# Power_Supply.net
KiCad netlist of a schematic drawn in Altium Designer
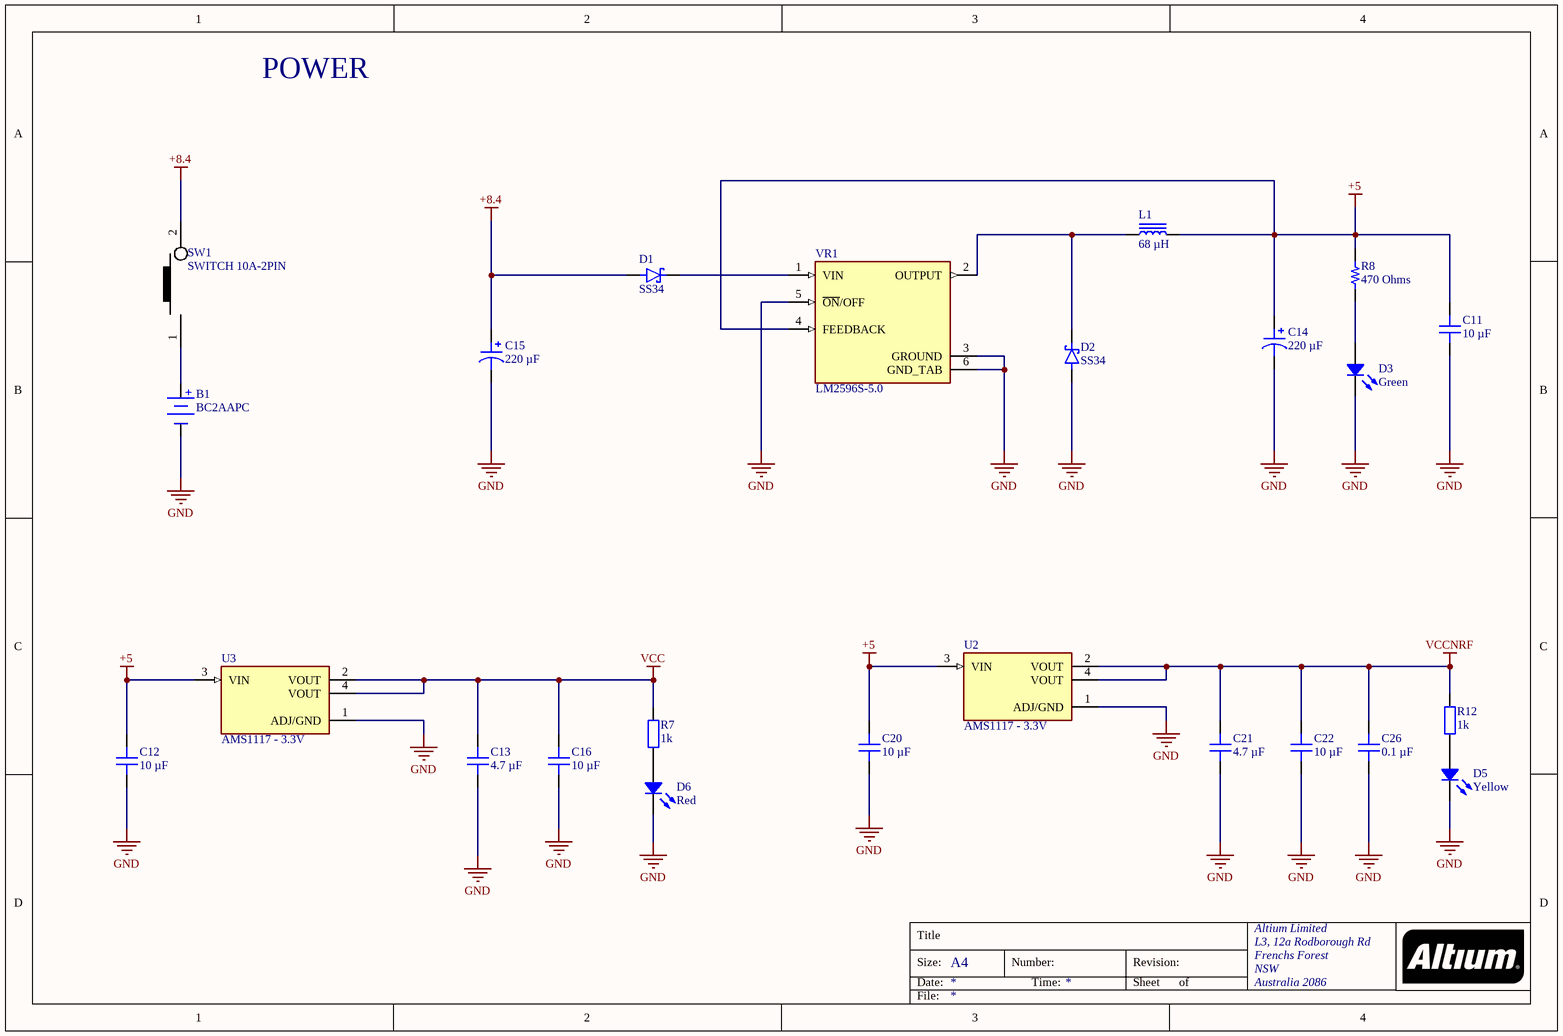
[diagram p0: Power_Supply.SchDoc]

(export (version "E")
  (design (tool "Eeschema 10.0.6"))
  (components
    (comp (ref "B1")
      (value "BC2AAPC")
      (footprint "MPD BC2AAPC")
      (description "BATTERY HOLDER AA 2 CELL PC PIN")
      (fields (field (name "MANUFACTURER") "MPD (Memory Protection Devices)"))
      (libsource (lib "Celestial Altium Library - altium_library") (part "MPD BC2AAPC"))
    )
    (comp (ref "C11")
      (value "10 µF")
      (footprint "CAP 0603_1608")
      (description "CAP CER 10UF 25V X5R 0603")
      (fields (field (name "PART NUMBER") "TMK107BBJ106MA-T") (field (name "MANUFACTURER") "Taiyo Yuden"))
      (libsource (lib "Celestial Altium Library - altium_library") (part "Capacitor"))
    )
    (comp (ref "C12")
      (value "10 µF")
      (footprint "CAP 0603_1608")
      (description "CAP CER 10UF 10V X6S 0603")
      (fields
        (field (name "PART NUMBER") "GRM188C81A106MA73D")
        (field (name "MANUFACTURER") "Murata Electronics")
      )
      (libsource (lib "Celestial Altium Library - altium_library") (part "Capacitor"))
    )
    (comp (ref "C13")
      (value "4.7 µF")
      (footprint "CAP 0603_1608")
      (description "CAP CER 4.7UF 10V X5R 0603")
      (fields (field (name "PART NUMBER") "LMK107BJ475MAHT") (field (name "MANUFACTURER") "Taiyo Yuden"))
      (libsource (lib "Celestial Altium Library - altium_library") (part "Capacitor"))
    )
    (comp (ref "C14")
      (value "220 µF")
      (footprint "CAP ALSMD 8.3MM H10.5MM")
      (description "CAP ALUM 220UF 20% 25V SMD")
      (fields (field (name "PART NUMBER") "VZH221M1ETR-0810S") (field (name "MANUFACTURER") "SURGE"))
      (libsource (lib "Celestial Altium Library - altium_library") (part "Polarised Capacitor"))
    )
    (comp (ref "C15")
      (value "220 µF")
      (footprint "CAP ALSMD 8.3MM H10.5MM")
      (description "CAP ALUM 220UF 20% 25V SMD")
      (fields (field (name "PART NUMBER") "VZH221M1ETR-0810S") (field (name "MANUFACTURER") "SURGE"))
      (libsource (lib "Celestial Altium Library - altium_library") (part "Polarised Capacitor"))
    )
    (comp (ref "C16")
      (value "10 µF")
      (footprint "CAP 0603_1608")
      (description "CAP CER 10UF 10V X6S 0603")
      (fields
        (field (name "PART NUMBER") "GRM188C81A106MA73D")
        (field (name "MANUFACTURER") "Murata Electronics")
      )
      (libsource (lib "Celestial Altium Library - altium_library") (part "Capacitor"))
    )
    (comp (ref "C20")
      (value "10 µF")
      (footprint "CAP 0603_1608")
      (description "CAP CER 10UF 10V X6S 0603")
      (fields
        (field (name "PART NUMBER") "GRM188C81A106MA73D")
        (field (name "MANUFACTURER") "Murata Electronics")
      )
      (libsource (lib "Celestial Altium Library - altium_library") (part "Capacitor"))
    )
    (comp (ref "C21")
      (value "4.7 µF")
      (footprint "CAP 0603_1608")
      (description "CAP CER 4.7UF 10V X5R 0603")
      (fields (field (name "PART NUMBER") "LMK107BJ475MAHT") (field (name "MANUFACTURER") "Taiyo Yuden"))
      (libsource (lib "Celestial Altium Library - altium_library") (part "Capacitor"))
    )
    (comp (ref "C22")
      (value "10 µF")
      (footprint "CAP 0603_1608")
      (description "CAP CER 10UF 10V X6S 0603")
      (fields
        (field (name "PART NUMBER") "GRM188C81A106MA73D")
        (field (name "MANUFACTURER") "Murata Electronics")
      )
      (libsource (lib "Celestial Altium Library - altium_library") (part "Capacitor"))
    )
    (comp (ref "C26")
      (value "0.1 µF")
      (footprint "CAP 0603_1608")
      (description "CAP CER 0.1UF 16V X7R 0603")
      (fields (field (name "PART NUMBER") "KGM15AR71C104MT") (field (name "MANUFACTURER") "KYOCERA AVX"))
      (libsource (lib "Celestial Altium Library - altium_library") (part "Capacitor"))
    )
    (comp (ref "D1")
      (value "SS34")
      (footprint "DIOM7959X265N")
      (description "Diode Schottky 40 V 3A Surface Mount SMC (DO-214AB)")
      (fields (field (name "MF") "onsemi"))
      (libsource (lib "SS34") (part "SS34"))
    )
    (comp (ref "D2")
      (value "SS34")
      (footprint "DIOM7959X265N")
      (description "Diode Schottky 40 V 3A Surface Mount SMC (DO-214AB)")
      (fields (field (name "MF") "onsemi"))
      (libsource (lib "SS34") (part "SS34"))
    )
    (comp (ref "D3")
      (value "Green")
      (footprint "LED 0402_1005 GREEN")
      (description "LED GREEN CLEAR 0402 SMD")
      (fields (field (name "PART NUMBER") "XZVGR68W-3") (field (name "MANUFACTURER") "SunLED"))
      (libsource (lib "Celestial Altium Library - altium_library") (part "LED"))
    )
    (comp (ref "D5")
      (value "Yellow")
      (footprint "LED 0402_1005 YELLOW")
      (description "LED YELLOW CLEAR 0402 SMD")
      (fields (field (name "PART NUMBER") "XZMYR68W-3") (field (name "MANUFACTURER") "SunLED"))
      (libsource (lib "Celestial Altium Library - altium_library") (part "LED"))
    )
    (comp (ref "D6")
      (value "Red")
      (footprint "LED 0402_1005 RED")
      (description "LED RED CLEAR 0402 SMD")
      (fields (field (name "PART NUMBER") "150040RS73220") (field (name "MANUFACTURER") "Würth Elektronik"))
      (libsource (lib "Celestial Altium Library - altium_library") (part "LED"))
    )
    (comp (ref "L1")
      (value "68 µH")
      (footprint "WURTH WE-PD 1210")
      (description "FIXED IND 68UH 3.2A 89 MOHM SMD")
      (fields (field (name "PART NUMBER") "7447709680") (field (name "MANUFACTURER") "Würth Elektronik"))
      (libsource (lib "Celestial Altium Library - altium_library") (part "Inductor"))
    )
    (comp (ref "R7")
      (value "1k")
      (footprint "tro smd 0603")
      (description "Dán")
      (libsource (lib "Dien Tro") (part "Tro 0603 1% 1k"))
    )
    (comp (ref "R8")
      (value "470 Ohms")
      (footprint "RES 0603_1608")
      (description "RES 470 OHM 0.1% 1/10W 0603")
      (fields
        (field (name "PART NUMBER") "RN73R1JTTD4700B25")
        (field (name "MANUFACTURER") "KOA Speer Electronics, Inc.")
      )
      (libsource (lib "Celestial Altium Library - altium_library") (part "Resistor"))
    )
    (comp (ref "R12")
      (value "1k")
      (footprint "tro smd 0603")
      (description "Dán")
      (libsource (lib "Dien Tro") (part "Tro 0603 1% 1k"))
    )
    (comp (ref "SW1")
      (value "SWITCH 10A-2PIN")
      (footprint "SW_2ARS_TH")
      (description "Rocker Switch SPST 16A (AC), 10A (DC) 250V Panel Mount, Snap-In")
      (fields
        (field (name "MANUFACTURER") "Würth Elektronik")
        (field (name "MANUFACTURER PART NUMBER") "471005264153")
      )
      (libsource (lib "Component") (part "SW1_RS-471005264153-TH"))
    )
    (comp (ref "U2")
      (value "AMS1117 - 3.3V")
      (footprint "SOT229P700X180-4N")
      (description "1A LOW DROPOUT VOLTAGE REGULATOR SOT-223")
      (fields (field (name "MP") "AMS1117") (field (name "MF") "Advanced Monolithic Systems"))
      (libsource (lib "AMS1117") (part "AMS1117"))
    )
    (comp (ref "U3")
      (value "AMS1117 - 3.3V")
      (footprint "SOT229P700X180-4N")
      (description "1A LOW DROPOUT VOLTAGE REGULATOR SOT-223")
      (fields (field (name "MP") "AMS1117") (field (name "MF") "Advanced Monolithic Systems"))
      (libsource (lib "AMS1117") (part "AMS1117"))
    )
    (comp (ref "VR1")
      (value "LM2596S-5.0")
      (footprint "TO170P1524X483-6N")
      (description "SIMPLE SWITCHER&reg; 4.5V to 40V, 3A Low Component Count Step-Down Regulator")
      (fields (field (name "MP") "LM2596S-5.0/NOPB") (field (name "MF") "Texas Instruments"))
      (libsource (lib "LM2596S-5.0") (part "LM2596S-5.0"))
    )
  )
  (nets
    (net (code "1") (name "+5") (class "Default")
      (node (ref "C11") (pin "2") (pinfunction "2_2") (pintype "passive"))
      (node (ref "C12") (pin "2") (pinfunction "2_2") (pintype "passive"))
      (node (ref "C14") (pin "1") (pinfunction "1_1") (pintype "passive"))
      (node (ref "C20") (pin "2") (pinfunction "2_2") (pintype "passive"))
      (node (ref "L1") (pin "2") (pinfunction "2_2") (pintype "passive"))
      (node (ref "R8") (pin "2") (pinfunction "2_2") (pintype "passive"))
      (node (ref "U2") (pin "3") (pinfunction "VIN_3") (pintype "input"))
      (node (ref "U3") (pin "3") (pinfunction "VIN_3") (pintype "input"))
      (node (ref "VR1") (pin "4") (pinfunction "FEEDBACK_4") (pintype "input"))
    )
    (net (code "2") (name "+8.4") (class "Default")
      (node (ref "C15") (pin "1") (pinfunction "1_1") (pintype "passive"))
      (node (ref "D1") (pin "A") (pinfunction "A_A") (pintype "passive"))
      (node (ref "SW1") (pin "2") (pinfunction "2_2") (pintype "passive"))
    )
    (net (code "3") (name "GND") (class "Default")
      (node (ref "B1") (pin "2") (pinfunction "-_2") (pintype "passive"))
      (node (ref "C11") (pin "1") (pinfunction "1_1") (pintype "passive"))
      (node (ref "C12") (pin "1") (pinfunction "1_1") (pintype "passive"))
      (node (ref "C13") (pin "1") (pinfunction "1_1") (pintype "passive"))
      (node (ref "C14") (pin "2") (pinfunction "2_2") (pintype "passive"))
      (node (ref "C15") (pin "2") (pinfunction "2_2") (pintype "passive"))
      (node (ref "C16") (pin "1") (pinfunction "1_1") (pintype "passive"))
      (node (ref "C20") (pin "1") (pinfunction "1_1") (pintype "passive"))
      (node (ref "C21") (pin "1") (pinfunction "1_1") (pintype "passive"))
      (node (ref "C22") (pin "1") (pinfunction "1_1") (pintype "passive"))
      (node (ref "C26") (pin "1") (pinfunction "1_1") (pintype "passive"))
      (node (ref "D2") (pin "A") (pinfunction "A_A") (pintype "passive"))
      (node (ref "D3") (pin "2") (pinfunction "2_2") (pintype "passive"))
      (node (ref "D5") (pin "2") (pinfunction "2_2") (pintype "passive"))
      (node (ref "D6") (pin "2") (pinfunction "2_2") (pintype "passive"))
      (node (ref "U2") (pin "1") (pinfunction "ADJ/GND_1") (pintype "power_in"))
      (node (ref "U3") (pin "1") (pinfunction "ADJ/GND_1") (pintype "power_in"))
      (node (ref "VR1") (pin "3") (pinfunction "GROUND_3") (pintype "power_in"))
      (node (ref "VR1") (pin "5") (pinfunction "~{ON}/OFF_5") (pintype "input"))
      (node (ref "VR1") (pin "6") (pinfunction "GND_TAB_6") (pintype "power_in"))
    )
    (net (code "4") (name "Net-(B1-+)") (class "Default")
      (node (ref "B1") (pin "1") (pinfunction "+_1") (pintype "passive"))
      (node (ref "SW1") (pin "1") (pinfunction "1_1") (pintype "passive"))
    )
    (net (code "5") (name "Net-(D1-K)") (class "Default")
      (node (ref "D1") (pin "C") (pinfunction "K_C") (pintype "passive"))
      (node (ref "VR1") (pin "1") (pinfunction "VIN_1") (pintype "input"))
    )
    (net (code "6") (name "Net-(D2-K)") (class "Default")
      (node (ref "D2") (pin "C") (pinfunction "K_C") (pintype "passive"))
      (node (ref "L1") (pin "1") (pinfunction "1_1") (pintype "passive"))
      (node (ref "VR1") (pin "2") (pinfunction "OUTPUT_2") (pintype "output"))
    )
    (net (code "7") (name "Net-(D3-Pad1)") (class "Default")
      (node (ref "D3") (pin "1") (pinfunction "1_1") (pintype "passive"))
      (node (ref "R8") (pin "1") (pinfunction "1_1") (pintype "passive"))
    )
    (net (code "8") (name "Net-(D5-Pad1)") (class "Default")
      (node (ref "D5") (pin "1") (pinfunction "1_1") (pintype "passive"))
      (node (ref "R12") (pin "1") (pinfunction "1_1") (pintype "passive"))
    )
    (net (code "9") (name "Net-(D6-Pad1)") (class "Default")
      (node (ref "D6") (pin "1") (pinfunction "1_1") (pintype "passive"))
      (node (ref "R7") (pin "1") (pinfunction "1_1") (pintype "passive"))
    )
    (net (code "10") (name "VCC") (class "Default")
      (node (ref "C13") (pin "2") (pinfunction "2_2") (pintype "passive"))
      (node (ref "C16") (pin "2") (pinfunction "2_2") (pintype "passive"))
      (node (ref "R7") (pin "2") (pinfunction "2_2") (pintype "passive"))
      (node (ref "U3") (pin "2") (pinfunction "VOUT_2") (pintype "passive"))
      (node (ref "U3") (pin "4") (pinfunction "VOUT_4") (pintype "passive"))
    )
    (net (code "11") (name "VCCNRF") (class "Default")
      (node (ref "C21") (pin "2") (pinfunction "2_2") (pintype "passive"))
      (node (ref "C22") (pin "2") (pinfunction "2_2") (pintype "passive"))
      (node (ref "C26") (pin "2") (pinfunction "2_2") (pintype "passive"))
      (node (ref "R12") (pin "2") (pinfunction "2_2") (pintype "passive"))
      (node (ref "U2") (pin "2") (pinfunction "VOUT_2") (pintype "passive"))
      (node (ref "U2") (pin "4") (pinfunction "VOUT_4") (pintype "passive"))
    )
  )
)
